# SafetyCircuit.net
KiCad netlist of a schematic drawn in Altium Designer
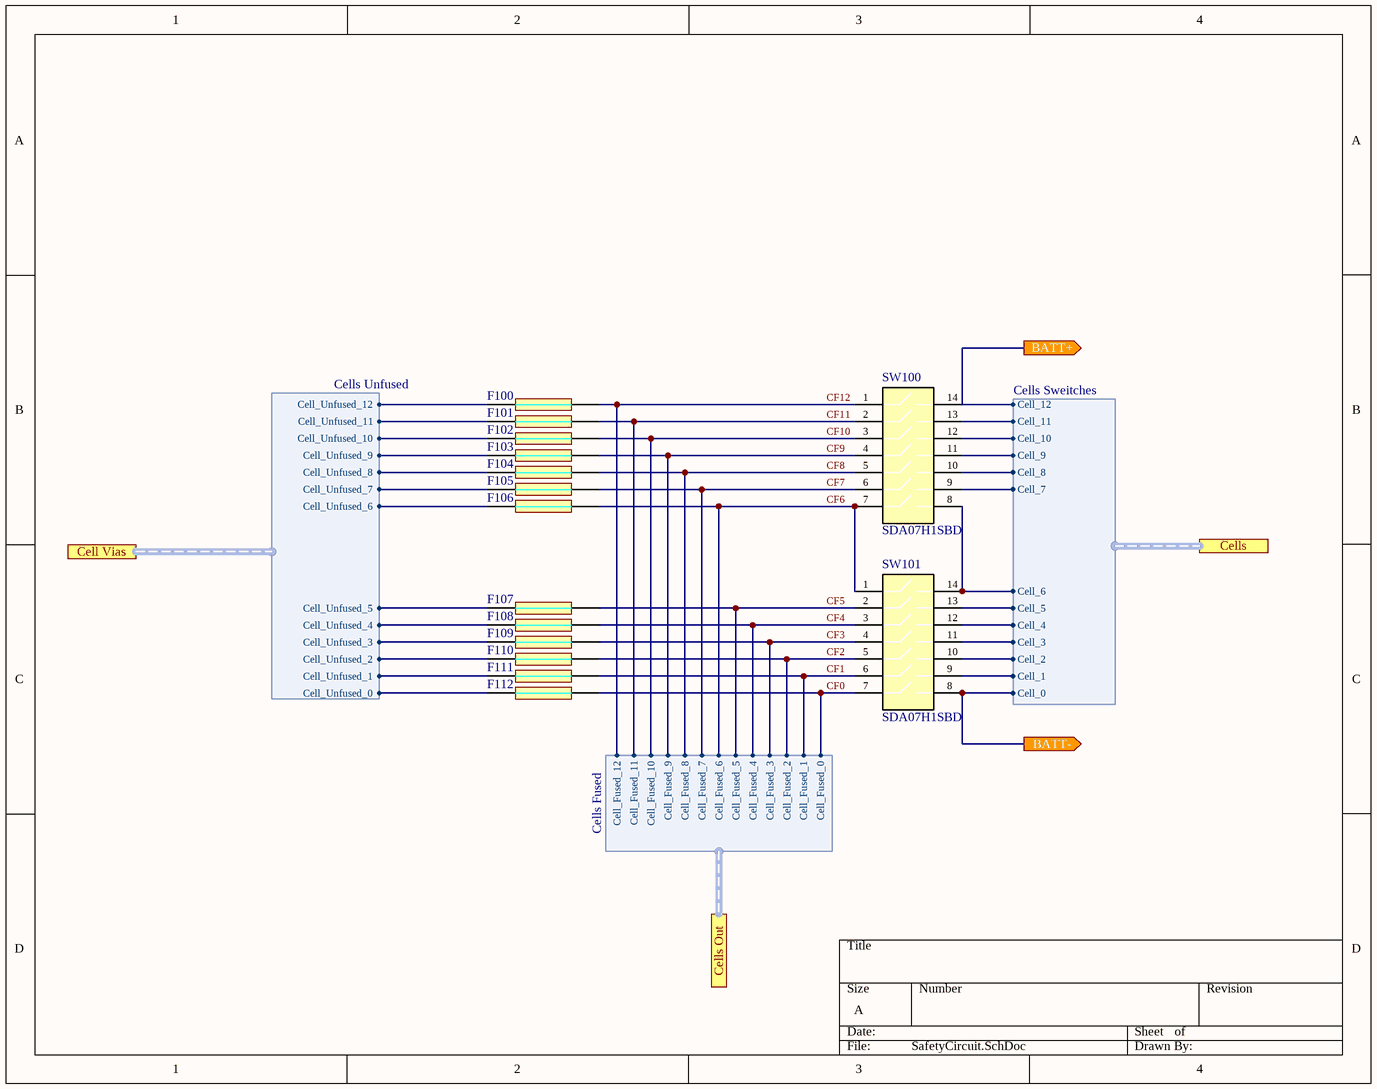
[diagram p0: SafetyCircuit.SchDoc]

(export (version "E")
  (design (tool "Eeschema 10.0.6"))
  (components
    (comp (ref "F100")
      (value "SFP200F")
      (footprint "DIOC3216X12N")
      (description "Surface Mount Fuses VERY FAST GLASS CER 63V 2A SZ 1206")
      (libsource (lib "SFP200F") (part "SFP200F"))
    )
    (comp (ref "F101")
      (value "SFP200F")
      (footprint "DIOC3216X12N")
      (description "Surface Mount Fuses VERY FAST GLASS CER 63V 2A SZ 1206")
      (libsource (lib "SFP200F") (part "SFP200F"))
    )
    (comp (ref "F102")
      (value "SFP200F")
      (footprint "DIOC3216X12N")
      (description "Surface Mount Fuses VERY FAST GLASS CER 63V 2A SZ 1206")
      (libsource (lib "SFP200F") (part "SFP200F"))
    )
    (comp (ref "F103")
      (value "SFP200F")
      (footprint "DIOC3216X12N")
      (description "Surface Mount Fuses VERY FAST GLASS CER 63V 2A SZ 1206")
      (libsource (lib "SFP200F") (part "SFP200F"))
    )
    (comp (ref "F104")
      (value "SFP200F")
      (footprint "DIOC3216X12N")
      (description "Surface Mount Fuses VERY FAST GLASS CER 63V 2A SZ 1206")
      (libsource (lib "SFP200F") (part "SFP200F"))
    )
    (comp (ref "F105")
      (value "SFP200F")
      (footprint "DIOC3216X12N")
      (description "Surface Mount Fuses VERY FAST GLASS CER 63V 2A SZ 1206")
      (libsource (lib "SFP200F") (part "SFP200F"))
    )
    (comp (ref "F106")
      (value "SFP200F")
      (footprint "DIOC3216X12N")
      (description "Surface Mount Fuses VERY FAST GLASS CER 63V 2A SZ 1206")
      (libsource (lib "SFP200F") (part "SFP200F"))
    )
    (comp (ref "F107")
      (value "SFP200F")
      (footprint "DIOC3216X12N")
      (description "Surface Mount Fuses VERY FAST GLASS CER 63V 2A SZ 1206")
      (libsource (lib "SFP200F") (part "SFP200F"))
    )
    (comp (ref "F108")
      (value "SFP200F")
      (footprint "DIOC3216X12N")
      (description "Surface Mount Fuses VERY FAST GLASS CER 63V 2A SZ 1206")
      (libsource (lib "SFP200F") (part "SFP200F"))
    )
    (comp (ref "F109")
      (value "SFP200F")
      (footprint "DIOC3216X12N")
      (description "Surface Mount Fuses VERY FAST GLASS CER 63V 2A SZ 1206")
      (libsource (lib "SFP200F") (part "SFP200F"))
    )
    (comp (ref "F110")
      (value "SFP200F")
      (footprint "DIOC3216X12N")
      (description "Surface Mount Fuses VERY FAST GLASS CER 63V 2A SZ 1206")
      (libsource (lib "SFP200F") (part "SFP200F"))
    )
    (comp (ref "F111")
      (value "SFP200F")
      (footprint "DIOC3216X12N")
      (description "Surface Mount Fuses VERY FAST GLASS CER 63V 2A SZ 1206")
      (libsource (lib "SFP200F") (part "SFP200F"))
    )
    (comp (ref "F112")
      (value "SFP200F")
      (footprint "DIOC3216X12N")
      (description "Surface Mount Fuses VERY FAST GLASS CER 63V 2A SZ 1206")
      (libsource (lib "SFP200F") (part "SFP200F"))
    )
    (comp (ref "SW100")
      (value "SDA07H1SBD")
      (footprint "7 pos Dip-Switch")
      (description "Dip Switch SPST 7 Position Surface Mount Slide (Standard) Actuator 25mA 24VDC")
      (libsource (lib "SDA07H1SBD") (part "Dip Switches"))
    )
    (comp (ref "SW101")
      (value "SDA07H1SBD")
      (footprint "7 pos Dip-Switch")
      (description "Dip Switch SPST 7 Position Surface Mount Slide (Standard) Actuator 25mA 24VDC")
      (libsource (lib "SDA07H1SBD") (part "Dip Switches"))
    )
  )
  (nets
    (net (code "5") (name "/BATT+") (class "Default")
      (node (ref "SW100") (pin "14") (pinfunction "14_14") (pintype "passive"))
    )
    (net (code "6") (name "/BATT-") (class "Default")
      (node (ref "SW101") (pin "8") (pinfunction "8_8") (pintype "passive"))
    )
    (net (code "7") (name "/CF0") (class "Default")
      (node (ref "F112") (pin "2") (pinfunction "2_2") (pintype "passive"))
      (node (ref "SW101") (pin "7") (pinfunction "7_7") (pintype "passive"))
    )
    (net (code "8") (name "/CF1") (class "Default")
      (node (ref "F111") (pin "2") (pinfunction "2_2") (pintype "passive"))
      (node (ref "SW101") (pin "6") (pinfunction "6_6") (pintype "passive"))
    )
    (net (code "9") (name "/CF2") (class "Default")
      (node (ref "F110") (pin "2") (pinfunction "2_2") (pintype "passive"))
      (node (ref "SW101") (pin "5") (pinfunction "5_5") (pintype "passive"))
    )
    (net (code "10") (name "/CF3") (class "Default")
      (node (ref "F109") (pin "2") (pinfunction "2_2") (pintype "passive"))
      (node (ref "SW101") (pin "4") (pinfunction "4_4") (pintype "passive"))
    )
    (net (code "11") (name "/CF4") (class "Default")
      (node (ref "F108") (pin "2") (pinfunction "2_2") (pintype "passive"))
      (node (ref "SW101") (pin "3") (pinfunction "3_3") (pintype "passive"))
    )
    (net (code "12") (name "/CF5") (class "Default")
      (node (ref "F107") (pin "2") (pinfunction "2_2") (pintype "passive"))
      (node (ref "SW101") (pin "2") (pinfunction "2_2") (pintype "passive"))
    )
    (net (code "13") (name "/CF6") (class "Default")
      (node (ref "F106") (pin "2") (pinfunction "2_2") (pintype "passive"))
      (node (ref "SW100") (pin "7") (pinfunction "7_7") (pintype "passive"))
      (node (ref "SW101") (pin "1") (pinfunction "1_1") (pintype "passive"))
    )
    (net (code "14") (name "/CF7") (class "Default")
      (node (ref "F105") (pin "2") (pinfunction "2_2") (pintype "passive"))
      (node (ref "SW100") (pin "6") (pinfunction "6_6") (pintype "passive"))
    )
    (net (code "15") (name "/CF8") (class "Default")
      (node (ref "F104") (pin "2") (pinfunction "2_2") (pintype "passive"))
      (node (ref "SW100") (pin "5") (pinfunction "5_5") (pintype "passive"))
    )
    (net (code "16") (name "/CF9") (class "Default")
      (node (ref "F103") (pin "2") (pinfunction "2_2") (pintype "passive"))
      (node (ref "SW100") (pin "4") (pinfunction "4_4") (pintype "passive"))
    )
    (net (code "17") (name "/CF10") (class "Default")
      (node (ref "F102") (pin "2") (pinfunction "2_2") (pintype "passive"))
      (node (ref "SW100") (pin "3") (pinfunction "3_3") (pintype "passive"))
    )
    (net (code "18") (name "/CF11") (class "Default")
      (node (ref "F101") (pin "2") (pinfunction "2_2") (pintype "passive"))
      (node (ref "SW100") (pin "2") (pinfunction "2_2") (pintype "passive"))
    )
    (net (code "19") (name "/CF12") (class "Default")
      (node (ref "F100") (pin "2") (pinfunction "2_2") (pintype "passive"))
      (node (ref "SW100") (pin "1") (pinfunction "1_1") (pintype "passive"))
    )
    (net (code "20") (name "/Cell_1") (class "Default")
      (node (ref "SW101") (pin "9") (pinfunction "9_9") (pintype "passive"))
    )
    (net (code "21") (name "/Cell_2") (class "Default")
      (node (ref "SW101") (pin "10") (pinfunction "10_10") (pintype "passive"))
    )
    (net (code "22") (name "/Cell_3") (class "Default")
      (node (ref "SW101") (pin "11") (pinfunction "11_11") (pintype "passive"))
    )
    (net (code "23") (name "/Cell_4") (class "Default")
      (node (ref "SW101") (pin "12") (pinfunction "12_12") (pintype "passive"))
    )
    (net (code "24") (name "/Cell_5") (class "Default")
      (node (ref "SW101") (pin "13") (pinfunction "13_13") (pintype "passive"))
    )
    (net (code "25") (name "/Cell_6") (class "Default")
      (node (ref "SW100") (pin "8") (pinfunction "8_8") (pintype "passive"))
      (node (ref "SW101") (pin "14") (pinfunction "14_14") (pintype "passive"))
    )
    (net (code "26") (name "/Cell_7") (class "Default")
      (node (ref "SW100") (pin "9") (pinfunction "9_9") (pintype "passive"))
    )
    (net (code "27") (name "/Cell_8") (class "Default")
      (node (ref "SW100") (pin "10") (pinfunction "10_10") (pintype "passive"))
    )
    (net (code "28") (name "/Cell_9") (class "Default")
      (node (ref "SW100") (pin "11") (pinfunction "11_11") (pintype "passive"))
    )
    (net (code "29") (name "/Cell_10") (class "Default")
      (node (ref "SW100") (pin "12") (pinfunction "12_12") (pintype "passive"))
    )
    (net (code "30") (name "/Cell_11") (class "Default")
      (node (ref "SW100") (pin "13") (pinfunction "13_13") (pintype "passive"))
    )
    (net (code "31") (name "/Cell_Unfused_0") (class "Default")
      (node (ref "F112") (pin "1") (pinfunction "1_1") (pintype "passive"))
    )
    (net (code "32") (name "/Cell_Unfused_1") (class "Default")
      (node (ref "F111") (pin "1") (pinfunction "1_1") (pintype "passive"))
    )
    (net (code "33") (name "/Cell_Unfused_2") (class "Default")
      (node (ref "F110") (pin "1") (pinfunction "1_1") (pintype "passive"))
    )
    (net (code "34") (name "/Cell_Unfused_3") (class "Default")
      (node (ref "F109") (pin "1") (pinfunction "1_1") (pintype "passive"))
    )
    (net (code "35") (name "/Cell_Unfused_4") (class "Default")
      (node (ref "F108") (pin "1") (pinfunction "1_1") (pintype "passive"))
    )
    (net (code "36") (name "/Cell_Unfused_5") (class "Default")
      (node (ref "F107") (pin "1") (pinfunction "1_1") (pintype "passive"))
    )
    (net (code "37") (name "/Cell_Unfused_6") (class "Default")
      (node (ref "F106") (pin "1") (pinfunction "1_1") (pintype "passive"))
    )
    (net (code "38") (name "/Cell_Unfused_7") (class "Default")
      (node (ref "F105") (pin "1") (pinfunction "1_1") (pintype "passive"))
    )
    (net (code "39") (name "/Cell_Unfused_8") (class "Default")
      (node (ref "F104") (pin "1") (pinfunction "1_1") (pintype "passive"))
    )
    (net (code "40") (name "/Cell_Unfused_9") (class "Default")
      (node (ref "F103") (pin "1") (pinfunction "1_1") (pintype "passive"))
    )
    (net (code "41") (name "/Cell_Unfused_10") (class "Default")
      (node (ref "F102") (pin "1") (pinfunction "1_1") (pintype "passive"))
    )
    (net (code "42") (name "/Cell_Unfused_11") (class "Default")
      (node (ref "F101") (pin "1") (pinfunction "1_1") (pintype "passive"))
    )
    (net (code "43") (name "/Cell_Unfused_12") (class "Default")
      (node (ref "F100") (pin "1") (pinfunction "1_1") (pintype "passive"))
    )
  )
)
